# door.net
KiCad netlist of a schematic drawn in EAGLE
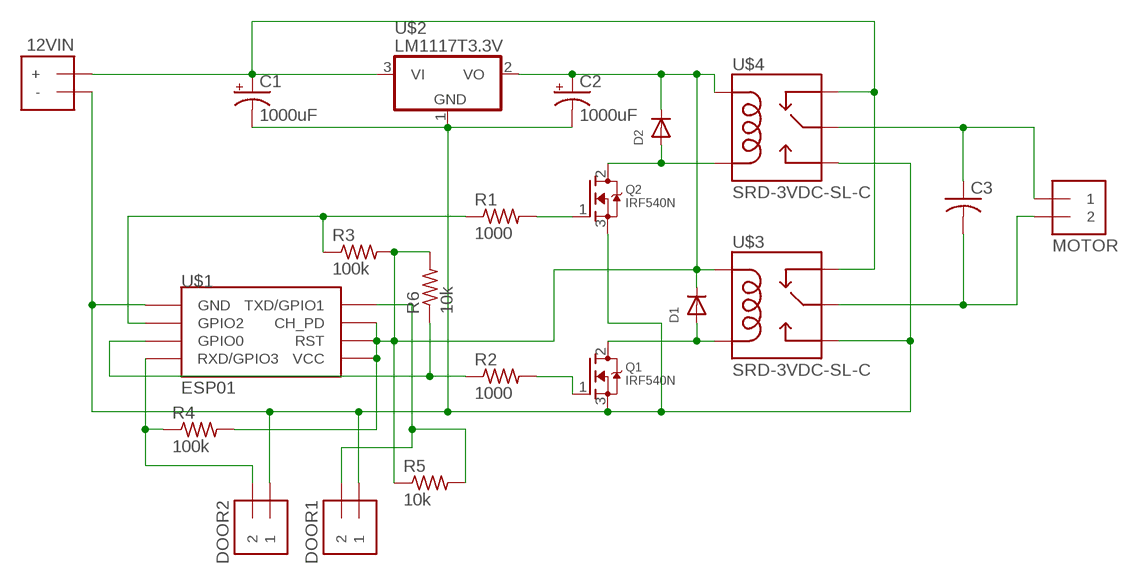
[diagram p0: schematic, sheet 1]

(export (version "E")
  (design (tool "Eeschema 10.0.6"))
  (components
    (comp (ref "12VIN")
      (value "1X2_-++-")
      (footprint "eagle-import:1X2_+-")
      (libsource (lib "eagle-import") (part "1X2_-++-"))
    )
    (comp (ref "C1")
      (value "1000uF")
      (footprint "eagle-import:E5-10,5")
      (libsource (lib "eagle-import") (part "CPOL-USE5-10.5"))
    )
    (comp (ref "C2")
      (value "1000uF")
      (footprint "eagle-import:E5-10,5")
      (libsource (lib "eagle-import") (part "CPOL-USE5-10.5"))
    )
    (comp (ref "C3")
      (value "C-US150-054X183")
      (footprint "eagle-import:C150-054X183")
      (libsource (lib "eagle-import") (part "C-US150-054X183"))
    )
    (comp (ref "D1")
      (value "DIODEDO-1N4148")
      (footprint "eagle-import:DO-1N4148")
      (libsource (lib "eagle-import") (part "DIODEDO-1N4148"))
    )
    (comp (ref "D2")
      (value "DIODEDO-1N4148")
      (footprint "eagle-import:DO-1N4148")
      (libsource (lib "eagle-import") (part "DIODEDO-1N4148"))
    )
    (comp (ref "DOOR1")
      (value "1X2_1212")
      (footprint "eagle-import:1X2_12")
      (libsource (lib "eagle-import") (part "1X2_1212"))
    )
    (comp (ref "DOOR2")
      (value "1X2_1212")
      (footprint "eagle-import:1X2_12")
      (libsource (lib "eagle-import") (part "1X2_1212"))
    )
    (comp (ref "MOTOR")
      (value "1X2_1221")
      (footprint "eagle-import:1X2_21")
      (libsource (lib "eagle-import") (part "1X2_1221"))
    )
    (comp (ref "Q1")
      (value "IRF540N")
      (footprint "eagle-import:TO220V")
      (libsource (lib "eagle-import") (part "MOSFET-NGDS_TO220V"))
    )
    (comp (ref "Q2")
      (value "IRF540N")
      (footprint "eagle-import:TO220V")
      (libsource (lib "eagle-import") (part "MOSFET-NGDS_TO220V"))
    )
    (comp (ref "R1")
      (value "1000")
      (footprint "eagle-import:0207_12")
      (libsource (lib "eagle-import") (part "R-US_0207/12"))
    )
    (comp (ref "R2")
      (value "1000")
      (footprint "eagle-import:0207_12")
      (libsource (lib "eagle-import") (part "R-US_0207/12"))
    )
    (comp (ref "R3")
      (value "100k")
      (footprint "eagle-import:0204_7")
      (libsource (lib "eagle-import") (part "R-US_0204/7"))
    )
    (comp (ref "R4")
      (value "100k")
      (footprint "eagle-import:0207_12")
      (libsource (lib "eagle-import") (part "R-US_0207/12"))
    )
    (comp (ref "R5")
      (value "10k")
      (footprint "eagle-import:0204_7")
      (libsource (lib "eagle-import") (part "R-US_0204/7"))
    )
    (comp (ref "R6")
      (value "10k")
      (footprint "eagle-import:0204_7")
      (libsource (lib "eagle-import") (part "R-US_0204/7"))
    )
    (comp (ref "U$1")
      (value "ESP01")
      (footprint "eagle-import:ESP01")
      (libsource (lib "eagle-import") (part "ESP01"))
    )
    (comp (ref "U$2")
      (value "LM1117T3.3V")
      (footprint "eagle-import:TO220V")
      (libsource (lib "eagle-import") (part "LD1117"))
    )
    (comp (ref "U$3")
      (value "SRD-3VDC-SL-C")
      (footprint "eagle-import:SRD-05VDC-SL-C")
      (libsource (lib "eagle-import") (part "RELAYPTH"))
    )
    (comp (ref "U$4")
      (value "SRD-3VDC-SL-C")
      (footprint "eagle-import:SRD-05VDC-SL-C")
      (libsource (lib "eagle-import") (part "RELAYPTH"))
    )
  )
  (nets
    (net (code "1") (name "Net-(C3-Pad1)") (class "Default")
      (node (ref "C3") (pin "1") (pinfunction "1_1") (pintype "passive"))
      (node (ref "MOTOR") (pin "1") (pinfunction "1_1") (pintype "passive"))
      (node (ref "U$4") (pin "SWCOMMON") (pinfunction "SWCOMMON_SWCOMMON") (pintype "bidirectional"))
    )
    (net (code "2") (name "Net-(C3-Pad2)") (class "Default")
      (node (ref "C3") (pin "2") (pinfunction "2_2") (pintype "passive"))
      (node (ref "MOTOR") (pin "2") (pinfunction "2_2") (pintype "passive"))
      (node (ref "U$3") (pin "SWCOMMON") (pinfunction "SWCOMMON_SWCOMMON") (pintype "bidirectional"))
    )
    (net (code "3") (name "Net-(Q1-D)") (class "Default")
      (node (ref "D1") (pin "A") (pinfunction "A_A") (pintype "passive"))
      (node (ref "Q1") (pin "2") (pinfunction "D_2") (pintype "bidirectional"))
      (node (ref "U$3") (pin "COIL0") (pinfunction "COIL0_COIL0") (pintype "bidirectional"))
    )
    (net (code "4") (name "Net-(Q1-G)") (class "Default")
      (node (ref "Q1") (pin "1") (pinfunction "G_1") (pintype "bidirectional"))
      (node (ref "R2") (pin "2") (pinfunction "2_2") (pintype "passive"))
    )
    (net (code "5") (name "Net-(Q1-S)") (class "Default")
      (node (ref "12VIN") (pin "-") (pinfunction "-_-") (pintype "passive"))
      (node (ref "C1") (pin "-") (pinfunction "-_-") (pintype "passive"))
      (node (ref "C2") (pin "-") (pinfunction "-_-") (pintype "passive"))
      (node (ref "DOOR1") (pin "1") (pinfunction "1_1") (pintype "passive"))
      (node (ref "DOOR2") (pin "1") (pinfunction "1_1") (pintype "passive"))
      (node (ref "Q1") (pin "3") (pinfunction "S_3") (pintype "bidirectional"))
      (node (ref "Q2") (pin "3") (pinfunction "S_3") (pintype "bidirectional"))
      (node (ref "U$1") (pin "GND") (pinfunction "GND_GND") (pintype "bidirectional"))
      (node (ref "U$2") (pin "1") (pinfunction "GND_1") (pintype "passive"))
      (node (ref "U$3") (pin "SWOPEN") (pinfunction "SWOPEN_SWOPEN") (pintype "bidirectional"))
      (node (ref "U$4") (pin "SWOPEN") (pinfunction "SWOPEN_SWOPEN") (pintype "bidirectional"))
    )
    (net (code "6") (name "Net-(Q2-D)") (class "Default")
      (node (ref "D2") (pin "A") (pinfunction "A_A") (pintype "passive"))
      (node (ref "Q2") (pin "2") (pinfunction "D_2") (pintype "bidirectional"))
      (node (ref "U$4") (pin "COIL0") (pinfunction "COIL0_COIL0") (pintype "bidirectional"))
    )
    (net (code "7") (name "Net-(Q2-G)") (class "Default")
      (node (ref "Q2") (pin "1") (pinfunction "G_1") (pintype "bidirectional"))
      (node (ref "R1") (pin "2") (pinfunction "2_2") (pintype "passive"))
    )
    (net (code "8") (name "Net-(R1-Pad1)") (class "Default")
      (node (ref "R1") (pin "1") (pinfunction "1_1") (pintype "passive"))
      (node (ref "R3") (pin "1") (pinfunction "1_1") (pintype "passive"))
      (node (ref "U$1") (pin "GPIO2") (pinfunction "GPIO2_GPIO2") (pintype "bidirectional"))
    )
    (net (code "9") (name "Net-(R2-Pad1)") (class "Default")
      (node (ref "R2") (pin "1") (pinfunction "1_1") (pintype "passive"))
      (node (ref "R6") (pin "1") (pinfunction "1_1") (pintype "passive"))
      (node (ref "U$1") (pin "GPIO0") (pinfunction "GPIO0_GPIO0") (pintype "bidirectional"))
    )
    (net (code "10") (name "Net-(U$1-RXD{slash}GPIO3)") (class "Default")
      (node (ref "DOOR2") (pin "2") (pinfunction "2_2") (pintype "passive"))
      (node (ref "R4") (pin "1") (pinfunction "1_1") (pintype "passive"))
      (node (ref "U$1") (pin "RX") (pinfunction "RXD/GPIO3_RX") (pintype "bidirectional"))
    )
    (net (code "11") (name "Net-(U$1-TXD{slash}GPIO1)") (class "Default")
      (node (ref "DOOR1") (pin "2") (pinfunction "2_2") (pintype "passive"))
      (node (ref "R5") (pin "2") (pinfunction "2_2") (pintype "passive"))
      (node (ref "U$1") (pin "TX") (pinfunction "TXD/GPIO1_TX") (pintype "bidirectional"))
    )
    (net (code "12") (name "Net-(U$2-VI)") (class "Default")
      (node (ref "12VIN") (pin "+") (pinfunction "+_+") (pintype "passive"))
      (node (ref "C1") (pin "+") (pinfunction "+_+") (pintype "passive"))
      (node (ref "U$2") (pin "3") (pinfunction "VI_3") (pintype "input"))
      (node (ref "U$3") (pin "SWCLOSED") (pinfunction "SWCLOSE_SWCLOSED") (pintype "bidirectional"))
      (node (ref "U$4") (pin "SWCLOSED") (pinfunction "SWCLOSE_SWCLOSED") (pintype "bidirectional"))
    )
    (net (code "13") (name "Net-(U$2-VO)") (class "Default")
      (node (ref "C2") (pin "+") (pinfunction "+_+") (pintype "passive"))
      (node (ref "D1") (pin "C") (pinfunction "C_C") (pintype "passive"))
      (node (ref "D2") (pin "C") (pinfunction "C_C") (pintype "passive"))
      (node (ref "R3") (pin "2") (pinfunction "2_2") (pintype "passive"))
      (node (ref "R4") (pin "2") (pinfunction "2_2") (pintype "passive"))
      (node (ref "R5") (pin "1") (pinfunction "1_1") (pintype "passive"))
      (node (ref "R6") (pin "2") (pinfunction "2_2") (pintype "passive"))
      (node (ref "U$1") (pin "CH_PD") (pinfunction "CH_PD_CH_PD") (pintype "bidirectional"))
      (node (ref "U$1") (pin "RST") (pinfunction "RST_RST") (pintype "bidirectional"))
      (node (ref "U$1") (pin "VCC") (pinfunction "VCC_VCC") (pintype "bidirectional"))
      (node (ref "U$2") (pin "2") (pinfunction "VO_2") (pintype "passive"))
      (node (ref "U$3") (pin "COIL1") (pinfunction "COIL1_COIL1") (pintype "bidirectional"))
      (node (ref "U$4") (pin "COIL1") (pinfunction "COIL1_COIL1") (pintype "bidirectional"))
    )
  )
)
